# Sensors.net
KiCad netlist of a schematic drawn in Altium Designer
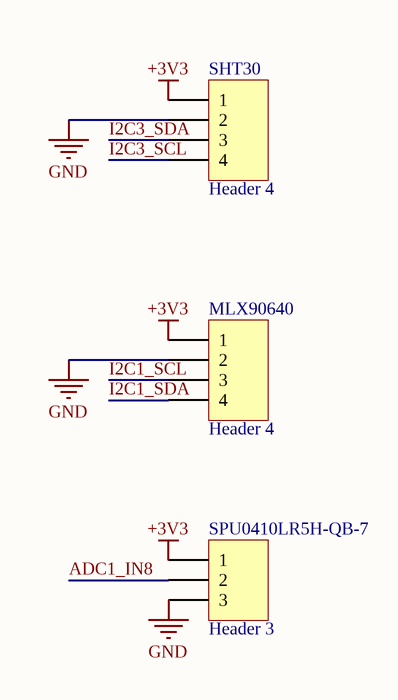
[diagram p0: Sensors.SchDoc]

(export (version "E")
  (design (tool "Eeschema 10.0.6"))
  (components
    (comp (ref "MLX90640")
      (value "Header 4")
      (footprint "HDR1X4")
      (description "Header, 4-Pin")
      (fields (field (name "PUBLISHER") "Altium Limited"))
      (libsource (lib "My Library") (part "Header 4"))
    )
    (comp (ref "SHT30")
      (value "Header 4")
      (footprint "HDR1X4")
      (description "Header, 4-Pin")
      (fields (field (name "PUBLISHER") "Altium Limited"))
      (libsource (lib "My Library") (part "Header 4"))
    )
    (comp (ref "SPU0410LR5H-QB-7")
      (value "Header 3")
      (footprint "HDR1X3")
      (description "Header, 3-Pin")
      (fields (field (name "PUBLISHER") "Altium Limited"))
      (libsource (lib "My Library") (part "Header 3"))
    )
  )
  (nets
    (net (code "1") (name "+3V3") (class "Default")
      (node (ref "MLX90640") (pin "1") (pinfunction "1_1") (pintype "passive"))
      (node (ref "SHT30") (pin "1") (pinfunction "1_1") (pintype "passive"))
      (node (ref "SPU0410LR5H-QB-7") (pin "1") (pinfunction "1_1") (pintype "passive"))
    )
    (net (code "2") (name "/ADC1_IN8") (class "Default")
      (node (ref "SPU0410LR5H-QB-7") (pin "2") (pinfunction "2_2") (pintype "passive"))
    )
    (net (code "3") (name "/I2C1_SCL") (class "Default")
      (node (ref "MLX90640") (pin "3") (pinfunction "3_3") (pintype "passive"))
    )
    (net (code "4") (name "/I2C1_SDA") (class "Default")
      (node (ref "MLX90640") (pin "4") (pinfunction "4_4") (pintype "passive"))
    )
    (net (code "5") (name "/I2C3_SCL") (class "Default")
      (node (ref "SHT30") (pin "4") (pinfunction "4_4") (pintype "passive"))
    )
    (net (code "6") (name "/I2C3_SDA") (class "Default")
      (node (ref "SHT30") (pin "3") (pinfunction "3_3") (pintype "passive"))
    )
    (net (code "7") (name "GND") (class "Default")
      (node (ref "MLX90640") (pin "2") (pinfunction "2_2") (pintype "passive"))
      (node (ref "SHT30") (pin "2") (pinfunction "2_2") (pintype "passive"))
      (node (ref "SPU0410LR5H-QB-7") (pin "3") (pinfunction "3_3") (pintype "passive"))
    )
  )
)
